# oshpark2_1_3-controller.net
KiCad netlist of a schematic drawn in EAGLE
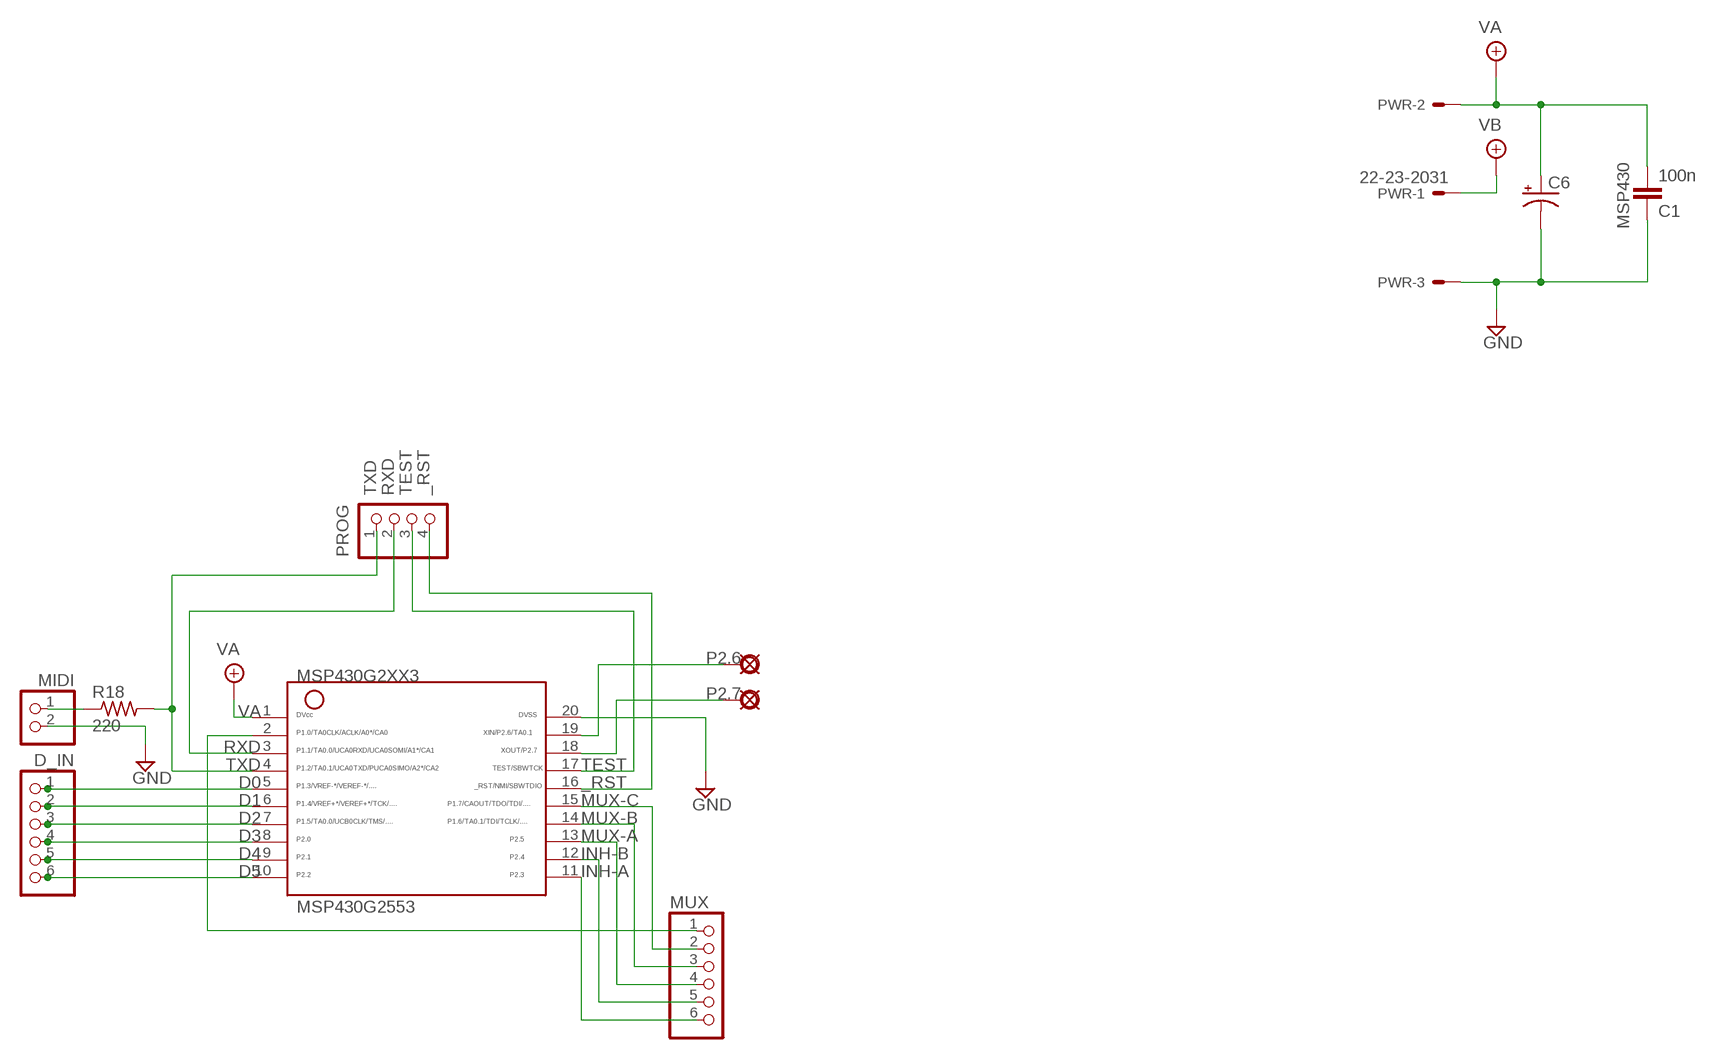
[diagram p0: schematic, sheet 1]

(export (version "E")
  (design (tool "Eeschema 10.0.6"))
  (components
    (comp (ref "C1")
      (value "100n")
      (footprint "eagle-import:050X030_050_3")
      (libsource (lib "eagle-import") (part "050X030_050"))
    )
    (comp (ref "C6")
      (value "0503")
      (footprint "eagle-import:050_020_3")
      (libsource (lib "eagle-import") (part "0503"))
    )
    (comp (ref "D_IN")
      (value "PINHD-1X6")
      (footprint "eagle-import:1X06")
      (libsource (lib "eagle-import") (part "PINHD-1X6"))
    )
    (comp (ref "MIDI")
      (value "PINHD-1X2")
      (footprint "eagle-import:1X02")
      (libsource (lib "eagle-import") (part "PINHD-1X2"))
    )
    (comp (ref "MSP430G2553")
      (value "G2XX3---N20")
      (footprint "eagle-import:N20")
      (libsource (lib "eagle-import") (part "G2XX3---N20"))
    )
    (comp (ref "MUX")
      (value "PINHD-1X6")
      (footprint "eagle-import:1X06")
      (libsource (lib "eagle-import") (part "PINHD-1X6"))
    )
    (comp (ref "P2.6")
      (value "PAD")
      (footprint "eagle-import:SQUARE")
      (libsource (lib "eagle-import") (part "PAD"))
    )
    (comp (ref "P2.7")
      (value "PAD")
      (footprint "eagle-import:SQUARE")
      (libsource (lib "eagle-import") (part "PAD"))
    )
    (comp (ref "PROG")
      (value "PINHD-1X4")
      (footprint "eagle-import:1X04")
      (libsource (lib "eagle-import") (part "PINHD-1X4"))
    )
    (comp (ref "PWR")
      (value "22-23-2031")
      (footprint "eagle-import:22-23-2031")
      (fields (field (name "MF") "MOLEX"))
      (libsource (lib "eagle-import") (part "22-23-2031"))
    )
    (comp (ref "R18")
      (value "220")
      (footprint "eagle-import:R0207_3")
      (libsource (lib "eagle-import") (part "6MM.3"))
    )
  )
  (nets
    (net (code "1") (name "/D0") (class "Default")
      (node (ref "D_IN") (pin "1") (pinfunction "1_1") (pintype "passive"))
      (node (ref "MSP430G2553") (pin "5") (pinfunction "5_5") (pintype "bidirectional"))
    )
    (net (code "2") (name "/D1") (class "Default")
      (node (ref "D_IN") (pin "2") (pinfunction "2_2") (pintype "passive"))
      (node (ref "MSP430G2553") (pin "6") (pinfunction "6_6") (pintype "bidirectional"))
    )
    (net (code "3") (name "/D2") (class "Default")
      (node (ref "D_IN") (pin "3") (pinfunction "3_3") (pintype "passive"))
      (node (ref "MSP430G2553") (pin "7") (pinfunction "7_7") (pintype "bidirectional"))
    )
    (net (code "4") (name "/D3") (class "Default")
      (node (ref "D_IN") (pin "4") (pinfunction "4_4") (pintype "passive"))
      (node (ref "MSP430G2553") (pin "8") (pinfunction "8_8") (pintype "bidirectional"))
    )
    (net (code "5") (name "/D4") (class "Default")
      (node (ref "D_IN") (pin "5") (pinfunction "5_5") (pintype "passive"))
      (node (ref "MSP430G2553") (pin "9") (pinfunction "9_9") (pintype "bidirectional"))
    )
    (net (code "6") (name "/D5") (class "Default")
      (node (ref "D_IN") (pin "6") (pinfunction "6_6") (pintype "passive"))
      (node (ref "MSP430G2553") (pin "10") (pinfunction "10_10") (pintype "bidirectional"))
    )
    (net (code "7") (name "/INH-A") (class "Default")
      (node (ref "MSP430G2553") (pin "11") (pinfunction "11_11") (pintype "bidirectional"))
      (node (ref "MUX") (pin "6") (pinfunction "6_6") (pintype "passive"))
    )
    (net (code "8") (name "/INH-B") (class "Default")
      (node (ref "MSP430G2553") (pin "12") (pinfunction "12_12") (pintype "bidirectional"))
      (node (ref "MUX") (pin "5") (pinfunction "5_5") (pintype "passive"))
    )
    (net (code "9") (name "/MUX-A") (class "Default")
      (node (ref "MSP430G2553") (pin "13") (pinfunction "13_13") (pintype "bidirectional"))
      (node (ref "MUX") (pin "4") (pinfunction "4_4") (pintype "passive"))
    )
    (net (code "10") (name "/MUX-B") (class "Default")
      (node (ref "MSP430G2553") (pin "14") (pinfunction "14_14") (pintype "bidirectional"))
      (node (ref "MUX") (pin "3") (pinfunction "3_3") (pintype "passive"))
    )
    (net (code "11") (name "/MUX-C") (class "Default")
      (node (ref "MSP430G2553") (pin "15") (pinfunction "15_15") (pintype "bidirectional"))
      (node (ref "MUX") (pin "2") (pinfunction "2_2") (pintype "passive"))
    )
    (net (code "12") (name "/RXD") (class "Default")
      (node (ref "MSP430G2553") (pin "3") (pinfunction "3_3") (pintype "bidirectional"))
      (node (ref "PROG") (pin "2") (pinfunction "2_2") (pintype "passive"))
    )
    (net (code "13") (name "/TEST") (class "Default")
      (node (ref "MSP430G2553") (pin "17") (pinfunction "17_17") (pintype "bidirectional"))
      (node (ref "PROG") (pin "3") (pinfunction "3_3") (pintype "passive"))
    )
    (net (code "14") (name "/TXD") (class "Default")
      (node (ref "MSP430G2553") (pin "4") (pinfunction "4_4") (pintype "bidirectional"))
      (node (ref "PROG") (pin "1") (pinfunction "1_1") (pintype "passive"))
      (node (ref "R18") (pin "2") (pinfunction "2_2") (pintype "passive"))
    )
    (net (code "15") (name "/_RST") (class "Default")
      (node (ref "MSP430G2553") (pin "16") (pinfunction "16_16") (pintype "bidirectional"))
      (node (ref "PROG") (pin "4") (pinfunction "4_4") (pintype "passive"))
    )
    (net (code "16") (name "GND") (class "Default")
      (node (ref "C1") (pin "1") (pinfunction "1_1") (pintype "passive"))
      (node (ref "C6") (pin "-") (pinfunction "-_-") (pintype "passive"))
      (node (ref "MIDI") (pin "2") (pinfunction "2_2") (pintype "passive"))
      (node (ref "MSP430G2553") (pin "20") (pinfunction "20_20") (pintype "bidirectional"))
      (node (ref "PWR") (pin "3") (pinfunction "S_3") (pintype "passive"))
    )
    (net (code "17") (name "Net-(MIDI-Pad1)") (class "Default")
      (node (ref "MIDI") (pin "1") (pinfunction "1_1") (pintype "passive"))
      (node (ref "R18") (pin "1") (pinfunction "1_1") (pintype "passive"))
    )
    (net (code "18") (name "Net-(MSP430G2553-Pad2)") (class "Default")
      (node (ref "MSP430G2553") (pin "2") (pinfunction "2_2") (pintype "bidirectional"))
      (node (ref "MUX") (pin "1") (pinfunction "1_1") (pintype "passive"))
    )
    (net (code "19") (name "Net-(P2.6-PAD)") (class "Default")
      (node (ref "MSP430G2553") (pin "19") (pinfunction "19_19") (pintype "bidirectional"))
      (node (ref "P2.6") (pin "1") (pinfunction "PAD_1") (pintype "passive"))
    )
    (net (code "20") (name "Net-(P2.7-PAD)") (class "Default")
      (node (ref "MSP430G2553") (pin "18") (pinfunction "18_18") (pintype "bidirectional"))
      (node (ref "P2.7") (pin "1") (pinfunction "PAD_1") (pintype "passive"))
    )
    (net (code "21") (name "VA") (class "Default")
      (node (ref "C1") (pin "2") (pinfunction "2_2") (pintype "passive"))
      (node (ref "C6") (pin "+") (pinfunction "+_+") (pintype "passive"))
      (node (ref "MSP430G2553") (pin "1") (pinfunction "1_1") (pintype "bidirectional"))
      (node (ref "PWR") (pin "2") (pinfunction "S_2") (pintype "passive"))
    )
    (net (code "22") (name "VB") (class "Default")
      (node (ref "PWR") (pin "1") (pinfunction "S_1") (pintype "passive"))
    )
  )
)
